# budik.net
KiCad netlist of a schematic drawn in EAGLE
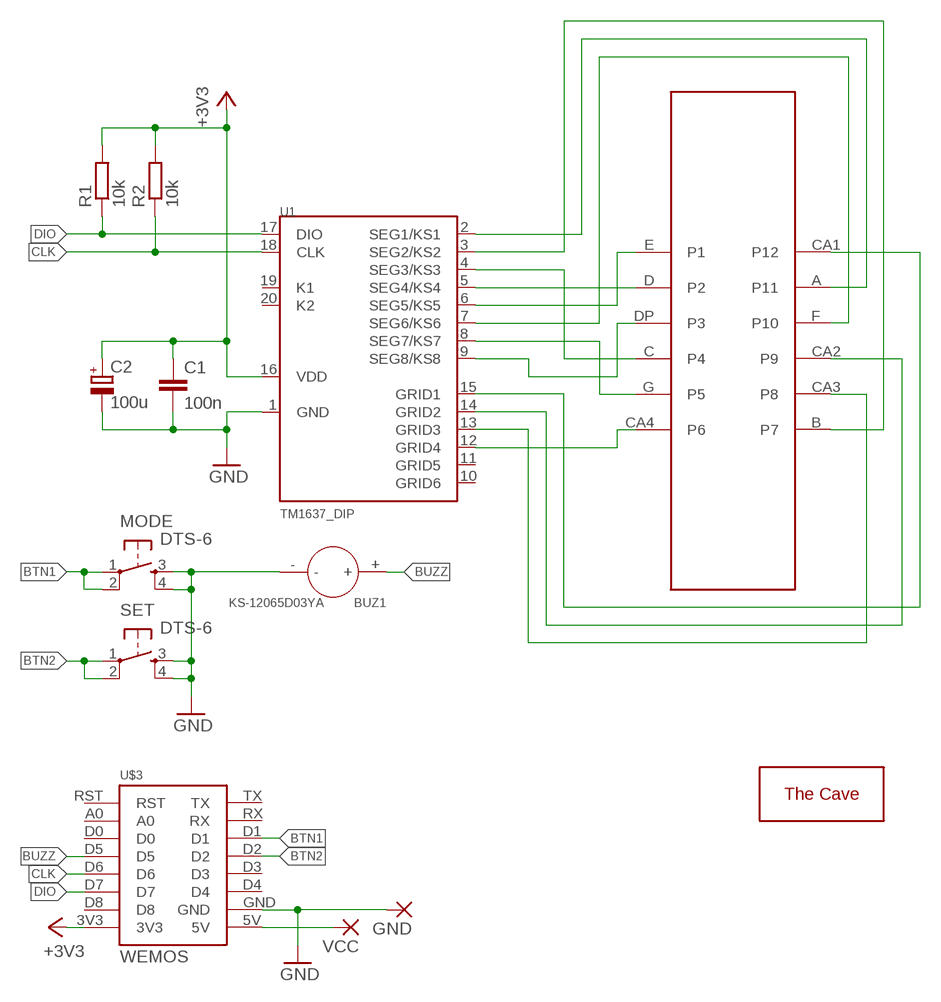
[diagram p0: schematic, sheet 1]

(export (version "E")
  (design (tool "Eeschema 10.0.6"))
  (components
    (comp (ref "BUZ1")
      (value "KS-12065D03YA")
      (footprint "eagle-import:BZ2-7.6-D12.0XH6.5MM")
      (libsource (lib "eagle-import") (part "DIP-BUZZER-3V(KS-12065D03YA)"))
    )
    (comp (ref "C1")
      (value "100n")
      (footprint "eagle-import:C025-025X050")
      (libsource (lib "eagle-import") (part "C-EU025-025X050"))
    )
    (comp (ref "C2")
      (value "100u")
      (footprint "eagle-import:E3,5-8")
      (libsource (lib "eagle-import") (part "CPOL-EUE3.5-8"))
    )
    (comp (ref "GND")
      (value "WIREPADSMD1,27-254")
      (footprint "eagle-import:SMD1,27-2,54")
      (libsource (lib "eagle-import") (part "WIREPADSMD1,27-254"))
    )
    (comp (ref "MODE")
      (value "DTS-6")
      (footprint "eagle-import:DTS-6")
      (libsource (lib "eagle-import") (part "DTS-6"))
    )
    (comp (ref "R1")
      (value "10k")
      (footprint "eagle-import:0207_7")
      (libsource (lib "eagle-import") (part "R-EU_0207/7"))
    )
    (comp (ref "R2")
      (value "10k")
      (footprint "eagle-import:0207_7")
      (libsource (lib "eagle-import") (part "R-EU_0207/7"))
    )
    (comp (ref "SET")
      (value "DTS-6")
      (footprint "eagle-import:DTS-6")
      (libsource (lib "eagle-import") (part "DTS-6"))
    )
    (comp (ref "U$1")
      (value "NFD-5642BX")
      (footprint "eagle-import:DISPLAY")
      (libsource (lib "eagle-import") (part "NFD-5642BX"))
    )
    (comp (ref "U$2")
      (value "THECAVE_LOGO_NEW_TOP_SMALL")
      (footprint "eagle-import:NEW_LOGO_SMALL_TOP")
      (libsource (lib "eagle-import") (part "THECAVE_LOGO_NEW_TOP_SMALL"))
    )
    (comp (ref "U$3")
      (value "WEMOS")
      (footprint "eagle-import:WEMOS")
      (libsource (lib "eagle-import") (part "WEMOS"))
    )
    (comp (ref "U1")
      (value "TM1637_DIP")
      (footprint "eagle-import:DIL20")
      (libsource (lib "eagle-import") (part "TM1637_DIP"))
    )
    (comp (ref "VCC")
      (value "WIREPADSMD1,27-254")
      (footprint "eagle-import:SMD1,27-2,54")
      (libsource (lib "eagle-import") (part "WIREPADSMD1,27-254"))
    )
  )
  (nets
    (net (code "1") (name "+3V3") (class "Default")
      (node (ref "C1") (pin "1") (pinfunction "1_1") (pintype "passive"))
      (node (ref "C2") (pin "+") (pinfunction "+_+") (pintype "passive"))
      (node (ref "R1") (pin "2") (pinfunction "2_2") (pintype "passive"))
      (node (ref "R2") (pin "2") (pinfunction "2_2") (pintype "passive"))
      (node (ref "U$3") (pin "3V3") (pinfunction "3V3_3V3") (pintype "bidirectional"))
      (node (ref "U1") (pin "16") (pinfunction "VDD_16") (pintype "bidirectional"))
    )
    (net (code "2") (name "BTN1") (class "Default")
      (node (ref "MODE") (pin "1") (pinfunction "1_1") (pintype "passive"))
      (node (ref "MODE") (pin "2") (pinfunction "2_2") (pintype "passive"))
      (node (ref "U$3") (pin "D1") (pinfunction "D1_D1") (pintype "bidirectional"))
    )
    (net (code "3") (name "BTN2") (class "Default")
      (node (ref "SET") (pin "1") (pinfunction "1_1") (pintype "passive"))
      (node (ref "SET") (pin "2") (pinfunction "2_2") (pintype "passive"))
      (node (ref "U$3") (pin "D2") (pinfunction "D2_D2") (pintype "bidirectional"))
    )
    (net (code "4") (name "BUZZ") (class "Default")
      (node (ref "BUZ1") (pin "+") (pinfunction "+_+") (pintype "bidirectional"))
      (node (ref "U$3") (pin "D5") (pinfunction "D5_D5") (pintype "bidirectional"))
    )
    (net (code "5") (name "CLK") (class "Default")
      (node (ref "R2") (pin "1") (pinfunction "1_1") (pintype "passive"))
      (node (ref "U$3") (pin "D6") (pinfunction "D6_D6") (pintype "bidirectional"))
      (node (ref "U1") (pin "18") (pinfunction "CLK_18") (pintype "bidirectional"))
    )
    (net (code "6") (name "DIO") (class "Default")
      (node (ref "R1") (pin "1") (pinfunction "1_1") (pintype "passive"))
      (node (ref "U$3") (pin "D7") (pinfunction "D7_D7") (pintype "bidirectional"))
      (node (ref "U1") (pin "17") (pinfunction "DIO_17") (pintype "bidirectional"))
    )
    (net (code "7") (name "GND") (class "Default")
      (node (ref "BUZ1") (pin "-") (pinfunction "-_-") (pintype "bidirectional"))
      (node (ref "C1") (pin "2") (pinfunction "2_2") (pintype "passive"))
      (node (ref "C2") (pin "-") (pinfunction "-_-") (pintype "passive"))
      (node (ref "GND") (pin "1") (pinfunction "P_1") (pintype "passive"))
      (node (ref "MODE") (pin "3") (pinfunction "3_3") (pintype "passive"))
      (node (ref "MODE") (pin "4") (pinfunction "4_4") (pintype "passive"))
      (node (ref "SET") (pin "3") (pinfunction "3_3") (pintype "passive"))
      (node (ref "SET") (pin "4") (pinfunction "4_4") (pintype "passive"))
      (node (ref "U$3") (pin "GND") (pinfunction "GND_GND") (pintype "bidirectional"))
      (node (ref "U1") (pin "1") (pinfunction "GND_1") (pintype "bidirectional"))
    )
    (net (code "8") (name "Net-(U$1-P1)") (class "Default")
      (node (ref "U$1") (pin "E") (pinfunction "P1_E") (pintype "bidirectional"))
      (node (ref "U1") (pin "6") (pinfunction "SEG5/KS5_6") (pintype "bidirectional"))
    )
    (net (code "9") (name "Net-(U$1-P2)") (class "Default")
      (node (ref "U$1") (pin "D") (pinfunction "P2_D") (pintype "bidirectional"))
      (node (ref "U1") (pin "5") (pinfunction "SEG4/KS4_5") (pintype "bidirectional"))
    )
    (net (code "10") (name "Net-(U$1-P3)") (class "Default")
      (node (ref "U$1") (pin "DP") (pinfunction "P3_DP") (pintype "bidirectional"))
      (node (ref "U1") (pin "9") (pinfunction "SEG8/KS8_9") (pintype "bidirectional"))
    )
    (net (code "11") (name "Net-(U$1-P4)") (class "Default")
      (node (ref "U$1") (pin "C") (pinfunction "P4_C") (pintype "bidirectional"))
      (node (ref "U1") (pin "4") (pinfunction "SEG3/KS3_4") (pintype "bidirectional"))
    )
    (net (code "12") (name "Net-(U$1-P5)") (class "Default")
      (node (ref "U$1") (pin "G") (pinfunction "P5_G") (pintype "bidirectional"))
      (node (ref "U1") (pin "8") (pinfunction "SEG7/KS7_8") (pintype "bidirectional"))
    )
    (net (code "13") (name "Net-(U$1-P6)") (class "Default")
      (node (ref "U$1") (pin "CA4") (pinfunction "P6_CA4") (pintype "bidirectional"))
      (node (ref "U1") (pin "12") (pinfunction "GRID4_12") (pintype "bidirectional"))
    )
    (net (code "14") (name "Net-(U$1-P7)") (class "Default")
      (node (ref "U$1") (pin "B") (pinfunction "P7_B") (pintype "bidirectional"))
      (node (ref "U1") (pin "3") (pinfunction "SEG2/KS2_3") (pintype "bidirectional"))
    )
    (net (code "15") (name "Net-(U$1-P8)") (class "Default")
      (node (ref "U$1") (pin "CA3") (pinfunction "P8_CA3") (pintype "bidirectional"))
      (node (ref "U1") (pin "13") (pinfunction "GRID3_13") (pintype "bidirectional"))
    )
    (net (code "16") (name "Net-(U$1-P9)") (class "Default")
      (node (ref "U$1") (pin "CA2") (pinfunction "P9_CA2") (pintype "bidirectional"))
      (node (ref "U1") (pin "14") (pinfunction "GRID2_14") (pintype "bidirectional"))
    )
    (net (code "17") (name "Net-(U$1-P10)") (class "Default")
      (node (ref "U$1") (pin "F") (pinfunction "P10_F") (pintype "bidirectional"))
      (node (ref "U1") (pin "7") (pinfunction "SEG6/KS6_7") (pintype "bidirectional"))
    )
    (net (code "18") (name "Net-(U$1-P11)") (class "Default")
      (node (ref "U$1") (pin "A") (pinfunction "P11_A") (pintype "bidirectional"))
      (node (ref "U1") (pin "2") (pinfunction "SEG1/KS1_2") (pintype "bidirectional"))
    )
    (net (code "19") (name "Net-(U$1-P12)") (class "Default")
      (node (ref "U$1") (pin "CA1") (pinfunction "P12_CA1") (pintype "bidirectional"))
      (node (ref "U1") (pin "15") (pinfunction "GRID1_15") (pintype "bidirectional"))
    )
    (net (code "20") (name "Net-(VCC-P)") (class "Default")
      (node (ref "U$3") (pin "5V") (pinfunction "5V_5V") (pintype "bidirectional"))
      (node (ref "VCC") (pin "1") (pinfunction "P_1") (pintype "passive"))
    )
    (net (code "21") (name "unconnected-(U$3-PadA0)") (class "Default")
      (node (ref "U$3") (pin "A0") (pinfunction "A0_A0") (pintype "bidirectional"))
    )
    (net (code "22") (name "unconnected-(U$3-PadD0)") (class "Default")
      (node (ref "U$3") (pin "D0") (pinfunction "D0_D0") (pintype "bidirectional"))
    )
    (net (code "23") (name "unconnected-(U$3-PadD3)") (class "Default")
      (node (ref "U$3") (pin "D3") (pinfunction "D3_D3") (pintype "bidirectional"))
    )
    (net (code "24") (name "unconnected-(U$3-PadD4)") (class "Default")
      (node (ref "U$3") (pin "D4") (pinfunction "D4_D4") (pintype "bidirectional"))
    )
    (net (code "25") (name "unconnected-(U$3-PadD8)") (class "Default")
      (node (ref "U$3") (pin "D8") (pinfunction "D8_D8") (pintype "bidirectional"))
    )
    (net (code "26") (name "unconnected-(U$3-PadRST)") (class "Default")
      (node (ref "U$3") (pin "RST") (pinfunction "RST_RST") (pintype "bidirectional"))
    )
    (net (code "27") (name "unconnected-(U$3-PadRX)") (class "Default")
      (node (ref "U$3") (pin "RX") (pinfunction "RX_RX") (pintype "bidirectional"))
    )
    (net (code "28") (name "unconnected-(U$3-PadTX)") (class "Default")
      (node (ref "U$3") (pin "TX") (pinfunction "TX_TX") (pintype "bidirectional"))
    )
    (net (code "29") (name "unconnected-(U1-GRID5-Pad11)") (class "Default")
      (node (ref "U1") (pin "11") (pinfunction "GRID5_11") (pintype "bidirectional"))
    )
    (net (code "30") (name "unconnected-(U1-GRID6-Pad10)") (class "Default")
      (node (ref "U1") (pin "10") (pinfunction "GRID6_10") (pintype "bidirectional"))
    )
    (net (code "31") (name "unconnected-(U1-K1-Pad19)") (class "Default")
      (node (ref "U1") (pin "19") (pinfunction "K1_19") (pintype "bidirectional"))
    )
    (net (code "32") (name "unconnected-(U1-K2-Pad20)") (class "Default")
      (node (ref "U1") (pin "20") (pinfunction "K2_20") (pintype "bidirectional"))
    )
  )
)
